# Mosfet_Driver_Circuit.net
KiCad netlist of a schematic drawn in Altium Designer
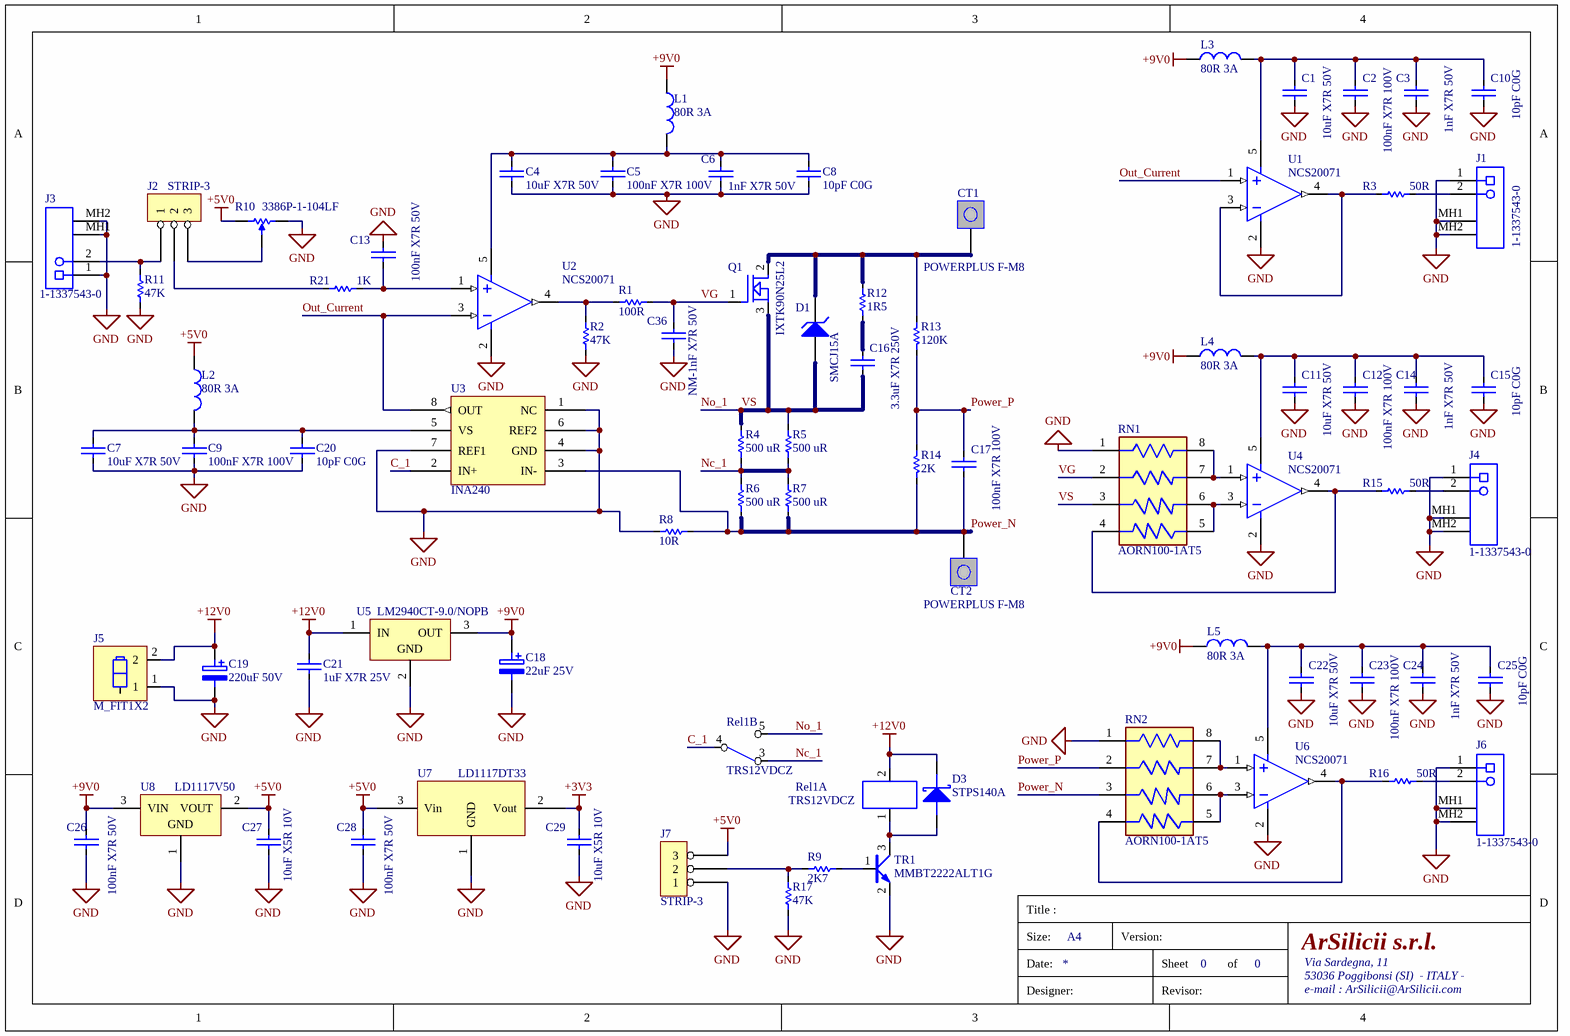
[diagram p0: Mosfet_Driver_Circuit.SchDoc]

(export (version "E")
  (design (tool "Eeschema 10.0.6"))
  (components
    (comp (ref "C1")
      (value "10uF X7R 50V")
      (footprint "1206")
      (description "Capacità")
      (fields
        (field (name "1 SUPPLIER PART NUMBER") "CL31B106KBHNNNE")
        (field (name "ARSILICII PART NUMBER") "CPC0232011")
      )
      (libsource (lib "Library_20-02-20") (part "CAP_10uF X7R 50V_1206"))
    )
    (comp (ref "C2")
      (value "100nF X7R 100V")
      (footprint "0805")
      (description "Capacità")
      (fields
        (field (name "1 SUPPLIER PART NUMBER") "CL21B104KCFSFNG")
        (field (name "2 SUPPLIER PART NUMBER") "1907331")
      )
      (libsource (lib "Library_20-02-20") (part "CAP_100nF X7R 100V_0805"))
    )
    (comp (ref "C3")
      (value "1nF X7R 50V")
      (footprint "0805")
      (description "Capacità")
      (fields
        (field (name "1 SUPPLIER PART NUMBER") "B37941K5102K60")
        (field (name "2 SUPPLIER PART NUMBER") "0805B102K5CT")
      )
      (libsource (lib "Library_20-02-20") (part "CAP_1nF X7R 50V_0805"))
    )
    (comp (ref "C4")
      (value "10uF X7R 50V")
      (footprint "1206")
      (description "Capacità")
      (fields
        (field (name "1 SUPPLIER PART NUMBER") "CL31B106KBHNNNE")
        (field (name "ARSILICII PART NUMBER") "CPC0232011")
      )
      (libsource (lib "Library_20-02-20") (part "CAP_10uF X7R 50V_1206"))
    )
    (comp (ref "C5")
      (value "100nF X7R 100V")
      (footprint "0805")
      (description "Capacità")
      (fields
        (field (name "1 SUPPLIER PART NUMBER") "CL21B104KCFSFNG")
        (field (name "2 SUPPLIER PART NUMBER") "1907331")
      )
      (libsource (lib "Library_20-02-20") (part "CAP_100nF X7R 100V_0805"))
    )
    (comp (ref "C6")
      (value "1nF X7R 50V")
      (footprint "0805")
      (description "Capacità")
      (fields
        (field (name "1 SUPPLIER PART NUMBER") "B37941K5102K60")
        (field (name "2 SUPPLIER PART NUMBER") "0805B102K5CT")
      )
      (libsource (lib "Library_20-02-20") (part "CAP_1nF X7R 50V_0805"))
    )
    (comp (ref "C7")
      (value "10uF X7R 50V")
      (footprint "1206")
      (description "Capacità")
      (fields
        (field (name "1 SUPPLIER PART NUMBER") "CL31B106KBHNNNE")
        (field (name "ARSILICII PART NUMBER") "CPC0232011")
      )
      (libsource (lib "Library_20-02-20") (part "CAP_10uF X7R 50V_1206"))
    )
    (comp (ref "C8")
      (value "10pF C0G")
      (footprint "0805")
      (description "Capacità")
      (fields (field (name "ARSILICII PART NUMBER") "CPC0614010"))
      (libsource (lib "Library_20-02-20") (part "CAP_10pF C0G_0805"))
    )
    (comp (ref "C9")
      (value "100nF X7R 100V")
      (footprint "0805")
      (description "Capacità")
      (fields
        (field (name "1 SUPPLIER PART NUMBER") "CL21B104KCFSFNG")
        (field (name "2 SUPPLIER PART NUMBER") "1907331")
      )
      (libsource (lib "Library_20-02-20") (part "CAP_100nF X7R 100V_0805"))
    )
    (comp (ref "C10")
      (value "10pF C0G")
      (footprint "0805")
      (description "Capacità")
      (fields (field (name "ARSILICII PART NUMBER") "CPC0614010"))
      (libsource (lib "Library_20-02-20") (part "CAP_10pF C0G_0805"))
    )
    (comp (ref "C11")
      (value "10uF X7R 50V")
      (footprint "1206")
      (description "Capacità")
      (fields
        (field (name "1 SUPPLIER PART NUMBER") "CL31B106KBHNNNE")
        (field (name "ARSILICII PART NUMBER") "CPC0232011")
      )
      (libsource (lib "Library_20-02-20") (part "CAP_10uF X7R 50V_1206"))
    )
    (comp (ref "C12")
      (value "100nF X7R 100V")
      (footprint "0805")
      (description "Capacità")
      (fields
        (field (name "1 SUPPLIER PART NUMBER") "CL21B104KCFSFNG")
        (field (name "2 SUPPLIER PART NUMBER") "1907331")
      )
      (libsource (lib "Library_20-02-20") (part "CAP_100nF X7R 100V_0805"))
    )
    (comp (ref "C13")
      (value "100nF X7R 50V")
      (footprint "0805")
      (description "Capacità")
      (fields
        (field (name "1 SUPPLIER PART NUMBER") "C0805C104K5RAC7800")
        (field (name "2 SUPPLIER PART NUMBER") "08055C104KAT2A AVX")
      )
      (libsource (lib "Library_20-02-20") (part "CAP_100nF X7R 50V_0805"))
    )
    (comp (ref "C14")
      (value "1nF X7R 50V")
      (footprint "0805")
      (description "Capacità")
      (fields
        (field (name "1 SUPPLIER PART NUMBER") "B37941K5102K60")
        (field (name "2 SUPPLIER PART NUMBER") "0805B102K5CT")
      )
      (libsource (lib "Library_20-02-20") (part "CAP_1nF X7R 50V_0805"))
    )
    (comp (ref "C15")
      (value "10pF C0G")
      (footprint "0805")
      (description "Capacità")
      (fields (field (name "ARSILICII PART NUMBER") "CPC0614010"))
      (libsource (lib "Library_20-02-20") (part "CAP_10pF C0G_0805"))
    )
    (comp (ref "C16")
      (value "3.3uF X7R 250V")
      (footprint "2220")
      (description "Capacità")
      (fields
        (field (name "1 SUPPLIER PART NUMBER") "2435506")
        (field (name "2 SUPPLIER PART NUMBER") "810-CGA9N3X7R2E105K")
      )
      (libsource (lib "Library_20-02-20") (part "CAP_1uF X7R 250V_2220"))
    )
    (comp (ref "C17")
      (value "100nF X7R 100V")
      (footprint "0805")
      (description "Capacità")
      (fields
        (field (name "1 SUPPLIER PART NUMBER") "CL21B104KCFSFNG")
        (field (name "2 SUPPLIER PART NUMBER") "1907331")
      )
      (libsource (lib "Library_20-02-20") (part "CAP_100nF X7R 100V_0805"))
    )
    (comp (ref "C18")
      (value "22uF 25V")
      (footprint "TANT_D")
      (description "Capacità polarizzata")
      (fields
        (field (name "1 SUPPLIER PART NUMBER") "KETT491D226K025AT")
        (field (name "ARSILICII PART NUMBER") "CPC0352022")
      )
      (libsource (lib "Library_20-02-20") (part "CAP_TANT_22uF 25V Case D"))
    )
    (comp (ref "C19")
      (value "220uF 50V")
      (footprint "C_G55")
      (description "Capacità polarizzata")
      (fields
        (field (name "2 SUPPLIER PART NUMBER") "5194346")
        (field (name "ARSILICII PART NUMBER") "CPC0402221")
      )
      (libsource (lib "Library_20-02-20") (part "CAP_EL_220uF 50V"))
    )
    (comp (ref "C20")
      (value "10pF C0G")
      (footprint "0805")
      (description "Capacità")
      (fields (field (name "ARSILICII PART NUMBER") "CPC0614010"))
      (libsource (lib "Library_20-02-20") (part "CAP_10pF C0G_0805"))
    )
    (comp (ref "C21")
      (value "1uF X7R 25V")
      (footprint "0805")
      (description "Capacità")
      (fields
        (field (name "1 SUPPLIER PART NUMBER") "CL21B105KAFNNNG")
        (field (name "ARSILICII PART NUMBER") "CPC0212002")
      )
      (libsource (lib "Library_20-02-20") (part "CAP_1uF X7R 25V_0805"))
    )
    (comp (ref "C22")
      (value "10uF X7R 50V")
      (footprint "1206")
      (description "Capacità")
      (fields
        (field (name "1 SUPPLIER PART NUMBER") "CL31B106KBHNNNE")
        (field (name "ARSILICII PART NUMBER") "CPC0232011")
      )
      (libsource (lib "Library_20-02-20") (part "CAP_10uF X7R 50V_1206"))
    )
    (comp (ref "C23")
      (value "100nF X7R 100V")
      (footprint "0805")
      (description "Capacità")
      (fields
        (field (name "1 SUPPLIER PART NUMBER") "CL21B104KCFSFNG")
        (field (name "2 SUPPLIER PART NUMBER") "1907331")
      )
      (libsource (lib "Library_20-02-20") (part "CAP_100nF X7R 100V_0805"))
    )
    (comp (ref "C24")
      (value "1nF X7R 50V")
      (footprint "0805")
      (description "Capacità")
      (fields
        (field (name "1 SUPPLIER PART NUMBER") "B37941K5102K60")
        (field (name "2 SUPPLIER PART NUMBER") "0805B102K5CT")
      )
      (libsource (lib "Library_20-02-20") (part "CAP_1nF X7R 50V_0805"))
    )
    (comp (ref "C25")
      (value "10pF C0G")
      (footprint "0805")
      (description "Capacità")
      (fields (field (name "ARSILICII PART NUMBER") "CPC0614010"))
      (libsource (lib "Library_20-02-20") (part "CAP_10pF C0G_0805"))
    )
    (comp (ref "C26")
      (value "100nF X7R 50V")
      (footprint "0805")
      (description "Capacità")
      (fields
        (field (name "1 SUPPLIER PART NUMBER") "C0805C104K5RAC7800")
        (field (name "2 SUPPLIER PART NUMBER") "08055C104KAT2A AVX")
      )
      (libsource (lib "Library_20-02-20") (part "CAP_100nF X7R 50V_0805"))
    )
    (comp (ref "C27")
      (value "10uF X5R 10V")
      (footprint "0805")
      (description "Capacità")
      (fields
        (field (name "1 SUPPLIER PART NUMBER") "CL21A106KPFNNNE")
        (field (name "ARSILICII PART NUMBER") "CPC0212010")
      )
      (libsource (lib "Library_20-02-20") (part "CAP_10uF X5R 10V_0805"))
    )
    (comp (ref "C28")
      (value "100nF X7R 50V")
      (footprint "0805")
      (description "Capacità")
      (fields
        (field (name "1 SUPPLIER PART NUMBER") "C0805C104K5RAC7800")
        (field (name "2 SUPPLIER PART NUMBER") "08055C104KAT2A AVX")
      )
      (libsource (lib "Library_20-02-20") (part "CAP_100nF X7R 50V_0805"))
    )
    (comp (ref "C29")
      (value "10uF X5R 10V")
      (footprint "0805")
      (description "Capacità")
      (fields
        (field (name "1 SUPPLIER PART NUMBER") "CL21A106KPFNNNE")
        (field (name "ARSILICII PART NUMBER") "CPC0212010")
      )
      (libsource (lib "Library_20-02-20") (part "CAP_10uF X5R 10V_0805"))
    )
    (comp (ref "C36")
      (value "NM-1nF X7R 50V")
      (footprint "0805")
      (description "Capacità")
      (fields
        (field (name "1 SUPPLIER PART NUMBER") "B37941K5102K60")
        (field (name "2 SUPPLIER PART NUMBER") "0805B102K5CT")
      )
      (libsource (lib "Library_20-02-20") (part "CAP_1nF X7R 50V_0805"))
    )
    (comp (ref "CT1")
      (value "POWERPLUS F-M8")
      (footprint "PowerPlus M8")
      (description "Singolo contatto")
      (fields
        (field (name "1 SUPPLIER PART NUMBER") "S98978")
        (field (name "ARSILICII PART NUMBER") "QC04000180")
      )
      (libsource (lib "Library_20-02-20") (part "PAD_POWERPLUS F-M8"))
    )
    (comp (ref "CT2")
      (value "POWERPLUS F-M8")
      (footprint "PowerPlus M8")
      (description "Singolo contatto")
      (fields
        (field (name "1 SUPPLIER PART NUMBER") "S98978")
        (field (name "ARSILICII PART NUMBER") "QC04000180")
      )
      (libsource (lib "") (part "PAD_POWERPLUS F-M8_1"))
    )
    (comp (ref "D1")
      (value "SMCJ15A")
      (footprint "LFUS-DO-214AB-2_V")
      (fields (field (name "MANUFACTURER") "Littelfuse"))
      (libsource (lib "Altium Content Vault") (part "DZEN-AK-2"))
    )
    (comp (ref "D3")
      (value "STPS140A")
      (footprint "SMA")
      (description "Diodo Schottky")
      (fields
        (field (name "MANUFACTURER") "STMicroelectronics")
        (field (name "1 SUPPLIER PART NUMBER") "STMSTPS140A")
      )
      (libsource (lib "Library_20-02-20") (part "DIODE SCHOTTKY_STPS140A"))
    )
    (comp (ref "J1")
      (value "1-1337543-0")
      (footprint "TECO-1-1337543-0_V")
      (fields (field (name "MANUFACTURER") "TE Connectivity"))
      (libsource (lib "Altium Content Vault") (part "CN-1P-F-R2_A"))
    )
    (comp (ref "J2")
      (value "STRIP-3")
      (footprint "SIP-3")
      (libsource (lib "Library_20-02-20") (part "HEADER 3"))
    )
    (comp (ref "J3")
      (value "1-1337543-0")
      (footprint "TECO-1-1337543-0_V")
      (fields (field (name "MANUFACTURER") "TE Connectivity"))
      (libsource (lib "") (part "CN-1P-F-R2_A_1"))
    )
    (comp (ref "J4")
      (value "1-1337543-0")
      (footprint "TECO-1-1337543-0_V")
      (fields (field (name "MANUFACTURER") "TE Connectivity"))
      (libsource (lib "Altium Content Vault") (part "CN-1P-F-R2_A"))
    )
    (comp (ref "J5")
      (value "M_FIT1X2")
      (footprint "M_FIT_JR1X2V")
      (description "Mini Fit Junior 2 poli")
      (fields (field (name "ARSILICII PART NUMBER") "QA02006000") (field (name "MANUFACTURER") "Molex"))
      (libsource (lib "Library_20-02-20") (part "M_FIT1X2"))
    )
    (comp (ref "J6")
      (value "1-1337543-0")
      (footprint "TECO-1-1337543-0_V")
      (fields (field (name "MANUFACTURER") "TE Connectivity"))
      (libsource (lib "Altium Content Vault") (part "CN-1P-F-R2_A"))
    )
    (comp (ref "J7") (value "STRIP-3") (footprint "SIP-3") (libsource (lib "") (part "HEADER 3_1")))
    (comp (ref "L1")
      (value "80R 3A")
      (footprint "1206")
      (description "Ferrite")
      (fields
        (field (name "1 SUPPLIER PART NUMBER") "3275550P")
        (field (name "ARSILICII PART NUMBER") "CPF0006000")
      )
      (libsource (lib "Library_20-02-20") (part "Ferrite 80R 3A"))
    )
    (comp (ref "L2")
      (value "80R 3A")
      (footprint "1206")
      (description "Ferrite")
      (fields
        (field (name "1 SUPPLIER PART NUMBER") "3275550P")
        (field (name "ARSILICII PART NUMBER") "CPF0006000")
      )
      (libsource (lib "Library_20-02-20") (part "Ferrite 80R 3A"))
    )
    (comp (ref "L3")
      (value "80R 3A")
      (footprint "1206")
      (description "Ferrite")
      (fields
        (field (name "1 SUPPLIER PART NUMBER") "3275550P")
        (field (name "ARSILICII PART NUMBER") "CPF0006000")
      )
      (libsource (lib "Library_20-02-20") (part "Ferrite 80R 3A"))
    )
    (comp (ref "L4")
      (value "80R 3A")
      (footprint "1206")
      (description "Ferrite")
      (fields
        (field (name "1 SUPPLIER PART NUMBER") "3275550P")
        (field (name "ARSILICII PART NUMBER") "CPF0006000")
      )
      (libsource (lib "Library_20-02-20") (part "Ferrite 80R 3A"))
    )
    (comp (ref "L5")
      (value "80R 3A")
      (footprint "1206")
      (description "Ferrite")
      (fields
        (field (name "1 SUPPLIER PART NUMBER") "3275550P")
        (field (name "ARSILICII PART NUMBER") "CPF0006000")
      )
      (libsource (lib "Library_20-02-20") (part "Ferrite 80R 3A"))
    )
    (comp (ref "Q1")
      (value "IXTK90N25L2")
      (footprint "Library_20-02-20:TO-247")
      (description "MOS CANALE N-250V-90A Linear")
      (fields
        (field (name "1 SUPPLIER PART NUMBER") "PB90N06S4-04")
        (field (name "2 SUPPLIER PART NUMBER") "826-9042P")
      )
      (libsource (lib "Library_20-02-20") (part "IXTK90N25L2"))
    )
    (comp (ref "R1")
      (value "100R")
      (footprint "0805")
      (description "Resistenza")
      (libsource (lib "Library_20-02-20") (part "RES_SMD"))
    )
    (comp (ref "R2")
      (value "47K")
      (footprint "0805")
      (description "Resistenza")
      (libsource (lib "Library_20-02-20") (part "RES_SMD"))
    )
    (comp (ref "R3")
      (value "50R")
      (footprint "0805")
      (description "Resistenza")
      (libsource (lib "Library_20-02-20") (part "RES_SMD"))
    )
    (comp (ref "R4")
      (value "500 uR")
      (footprint "2512")
      (description "Resistenza")
      (libsource (lib "Library_20-02-20") (part "RES_SMD"))
    )
    (comp (ref "R5")
      (value "500 uR")
      (footprint "2512")
      (description "Resistenza")
      (libsource (lib "Library_20-02-20") (part "RES_SMD"))
    )
    (comp (ref "R6")
      (value "500 uR")
      (footprint "2512")
      (description "Resistenza")
      (libsource (lib "Library_20-02-20") (part "RES_SMD"))
    )
    (comp (ref "R7")
      (value "500 uR")
      (footprint "2512")
      (description "Resistenza")
      (libsource (lib "Library_20-02-20") (part "RES_SMD"))
    )
    (comp (ref "R8")
      (value "10R")
      (footprint "1206")
      (description "Resistenza")
      (libsource (lib "Library_20-02-20") (part "RES_SMD"))
    )
    (comp (ref "R9")
      (value "2K7")
      (footprint "0805")
      (description "Resistenza")
      (libsource (lib "Library_20-02-20") (part "RES_SMD"))
    )
    (comp (ref "R10")
      (value "3386P-1-104LF")
      (footprint "BOUR-3386P")
      (fields (field (name "TOLERANCE") "10%") (field (name "MANUFACTURER") "Bourns"))
      (libsource (lib "Altium Content Vault") (part "RES-ADJ-3_A"))
    )
    (comp (ref "R11")
      (value "47K")
      (footprint "0805")
      (description "Resistenza")
      (libsource (lib "Library_20-02-20") (part "RES_SMD"))
    )
    (comp (ref "R12")
      (value "1R5")
      (footprint "2512")
      (description "Resistenza")
      (libsource (lib "Library_20-02-20") (part "RES_SMD"))
    )
    (comp (ref "R13")
      (value "120K")
      (footprint "2512")
      (description "Resistenza")
      (libsource (lib "Library_20-02-20") (part "RES_SMD"))
    )
    (comp (ref "R14")
      (value "2K")
      (footprint "2512")
      (description "Resistenza")
      (libsource (lib "Library_20-02-20") (part "RES_SMD"))
    )
    (comp (ref "R15")
      (value "50R")
      (footprint "0805")
      (description "Resistenza")
      (libsource (lib "Library_20-02-20") (part "RES_SMD"))
    )
    (comp (ref "R16")
      (value "50R")
      (footprint "0805")
      (description "Resistenza")
      (libsource (lib "Library_20-02-20") (part "RES_SMD"))
    )
    (comp (ref "R17")
      (value "47K")
      (footprint "0805")
      (description "Resistenza")
      (libsource (lib "Library_20-02-20") (part "RES_SMD"))
    )
    (comp (ref "R21")
      (value "1K")
      (footprint "0805")
      (description "Resistenza")
      (libsource (lib "Library_20-02-20") (part "RES_SMD"))
    )
    (comp (ref "Rel1")
      (value "TRS12VDCZ")
      (footprint "RELE_TRS")
      (description "Relay")
      (fields
        (field (name "2 SUPPLIER PART NUMBER") "FRS3M C-S DC12V")
        (field (name "3 SUPPLIER PART NUMBER") "R504D/012Z1F")
      )
      (libsource (lib "Library_20-02-20") (part "RELE'_TRS12VDCZ"))
    )
    (comp (ref "RN1")
      (value "AORN100-1AT5")
      (footprint "FP-AORN100-1AT5-IPC_C")
      (description "RES NETWORK 4 RES MULT OHM 8SOIC")
      (fields (field (name "MANUFACTURER") "Vishay") (field (name "TOLERANCE") "0.1%"))
      (libsource (lib "Altium Content Vault") (part "8441eaa576eb2593bca60d5301712c1"))
    )
    (comp (ref "RN2")
      (value "AORN100-1AT5")
      (footprint "FP-AORN100-1AT5-IPC_C")
      (description "RES NETWORK 4 RES MULT OHM 8SOIC")
      (fields (field (name "MANUFACTURER") "Vishay") (field (name "TOLERANCE") "0.1%"))
      (libsource (lib "Altium Content Vault") (part "8441eaa576eb2593bca60d5301712c1"))
    )
    (comp (ref "TR1")
      (value "MMBT2222ALT1G")
      (footprint "SOT-23")
      (description "NPN Transistor")
      (fields
        (field (name "1 SUPPLIER PART NUMBER") "SCGMMBT2222ALT1G")
        (field (name "2 SUPPLIER PART NUMBER") "1459098")
      )
      (libsource (lib "Library_20-02-20") (part "NPN_MMBT2222ALT1G"))
    )
    (comp (ref "U1")
      (value "NCS20071")
      (footprint "SOT-553-5")
      (description "Rail-to-Rail Input/Output, 3 MHz Op Amps")
      (fields
        (field (name "1 SUPPLIER PART NUMBER") "MCP6021-E/SN-ND")
        (field (name "MANUFACTURER") "Microchip Technology")
      )
      (libsource (lib "Library_20-02-20") (part "NCS20071"))
    )
    (comp (ref "U2")
      (value "NCS20071")
      (footprint "SOT-553-5")
      (description "Rail-to-Rail Input/Output, 3 MHz Op Amps")
      (fields
        (field (name "1 SUPPLIER PART NUMBER") "MCP6021-E/SN-ND")
        (field (name "MANUFACTURER") "Microchip Technology")
      )
      (libsource (lib "Library_20-02-20") (part "NCS20071"))
    )
    (comp (ref "U3")
      (value "INA240")
      (footprint "TSSOP-8")
      (description "Current sense amplifier")
      (libsource (lib "Library_20-02-20") (part "INA240"))
    )
    (comp (ref "U4")
      (value "NCS20071")
      (footprint "SOT-553-5")
      (description "Rail-to-Rail Input/Output, 3 MHz Op Amps")
      (fields
        (field (name "1 SUPPLIER PART NUMBER") "MCP6021-E/SN-ND")
        (field (name "MANUFACTURER") "Microchip Technology")
      )
      (libsource (lib "Library_20-02-20") (part "NCS20071"))
    )
    (comp (ref "U5")
      (value "LM2940CT-9.0/NOPB")
      (footprint "NDE0003A")
      (description "1A Low Dropout Regulator, 3-pin TO-220, Pb-Free")
      (fields (field (name "MANUFACTURER") "Texas Instruments"))
      (libsource (lib "Altium Content Vault") (part "PM-REG-LM2940-SIL3"))
    )
    (comp (ref "U6")
      (value "NCS20071")
      (footprint "SOT-553-5")
      (description "Rail-to-Rail Input/Output, 3 MHz Op Amps")
      (fields
        (field (name "1 SUPPLIER PART NUMBER") "MCP6021-E/SN-ND")
        (field (name "MANUFACTURER") "Microchip Technology")
      )
      (libsource (lib "Library_20-02-20") (part "NCS20071"))
    )
    (comp (ref "U7")
      (value "LD1117DT33")
      (footprint "TO-252-7805")
      (description "Regolatore Low Dropout")
      (fields
        (field (name "1 SUPPLIER PART NUMBER") "LD1117DT33TR TO252-3")
        (field (name "ARSILICII PART NUMBER") "IC01000010")
      )
      (libsource (lib "Library_20-02-20") (part "LD1117DT33"))
    )
    (comp (ref "U8")
      (value "LD1117V50")
      (footprint "TO220")
      (description "Fixed Low Drop Positive Voltage Regulator, 5V, 3-Pin TO-220")
      (libsource (lib "Altium Content Vault") (part "PM-REG-LD1117V-SIL3"))
    )
  )
  (nets
    (net (code "1") (name "+3V3") (class "Default")
      (node (ref "C29") (pin "1") (pintype "passive"))
      (node (ref "U7") (pin "2") (pinfunction "Vout_2") (pintype "power_in"))
    )
    (net (code "2") (name "+5V0") (class "Default")
      (node (ref "C27") (pin "1") (pintype "passive"))
      (node (ref "C28") (pin "1") (pintype "passive"))
      (node (ref "J7") (pin "3") (pinfunction "3_3") (pintype "passive"))
      (node (ref "L2") (pin "1") (pinfunction "1_1") (pintype "passive"))
      (node (ref "R10") (pin "1") (pinfunction "1_1") (pintype "passive"))
      (node (ref "U7") (pin "3") (pinfunction "Vin_3") (pintype "power_in"))
      (node (ref "U8") (pin "2") (pinfunction "VOUT_2") (pintype "power_in"))
    )
    (net (code "3") (name "+9V0") (class "Default")
      (node (ref "C18") (pin "1") (pintype "passive"))
      (node (ref "C26") (pin "1") (pintype "passive"))
      (node (ref "L1") (pin "1") (pinfunction "1_1") (pintype "passive"))
      (node (ref "L3") (pin "1") (pinfunction "1_1") (pintype "passive"))
      (node (ref "L4") (pin "1") (pinfunction "1_1") (pintype "passive"))
      (node (ref "L5") (pin "1") (pinfunction "1_1") (pintype "passive"))
      (node (ref "U5") (pin "3") (pinfunction "OUT_3") (pintype "power_in"))
      (node (ref "U8") (pin "3") (pinfunction "VIN_3") (pintype "power_in"))
    )
    (net (code "4") (name "+12V0") (class "Default")
      (node (ref "C19") (pin "1") (pintype "passive"))
      (node (ref "C21") (pin "1") (pintype "passive"))
      (node (ref "D3") (pin "K") (pinfunction "K_K") (pintype "passive"))
      (node (ref "J5") (pin "2") (pinfunction "2_2") (pintype "passive"))
      (node (ref "Rel1") (pin "2") (pintype "passive"))
      (node (ref "U5") (pin "1") (pinfunction "IN_1") (pintype "power_in"))
    )
    (net (code "5") (name "/C_1") (class "Default")
      (node (ref "Rel1") (pin "4") (pintype "passive"))
      (node (ref "U3") (pin "2") (pinfunction "IN+_2") (pintype "tri_state"))
    )
    (net (code "6") (name "/Nc_1") (class "Default")
      (node (ref "R4") (pin "2") (pinfunction "2_2") (pintype "passive"))
      (node (ref "R5") (pin "2") (pinfunction "2_2") (pintype "passive"))
      (node (ref "R6") (pin "1") (pinfunction "1_1") (pintype "passive"))
      (node (ref "R7") (pin "1") (pinfunction "1_1") (pintype "passive"))
      (node (ref "Rel1") (pin "3") (pintype "passive"))
    )
    (net (code "7") (name "/No_1") (class "Default")
      (node (ref "C16") (pin "2") (pintype "passive"))
      (node (ref "D1") (pin "1") (pinfunction "A_1") (pintype "passive"))
      (node (ref "Q1") (pin "3") (pinfunction "SOURCE_3") (pintype "passive"))
      (node (ref "R4") (pin "1") (pinfunction "1_1") (pintype "passive"))
      (node (ref "R5") (pin "1") (pinfunction "1_1") (pintype "passive"))
      (node (ref "RN1") (pin "3") (pinfunction "3_3") (pintype "passive"))
      (node (ref "Rel1") (pin "5") (pintype "passive"))
    )
    (net (code "8") (name "/Out_Current") (class "Default")
      (node (ref "U1") (pin "1") (pintype "input"))
      (node (ref "U2") (pin "3") (pintype "input"))
      (node (ref "U3") (pin "8") (pinfunction "OUT_8") (pintype "output"))
    )
    (net (code "9") (name "/Power_N") (class "Default")
      (node (ref "C17") (pin "2") (pintype "passive"))
      (node (ref "CT2") (pin "1") (pinfunction "1_1") (pintype "passive"))
      (node (ref "R14") (pin "2") (pinfunction "2_2") (pintype "passive"))
      (node (ref "R6") (pin "2") (pinfunction "2_2") (pintype "passive"))
      (node (ref "R7") (pin "2") (pinfunction "2_2") (pintype "passive"))
      (node (ref "R8") (pin "1") (pinfunction "1_1") (pintype "passive"))
      (node (ref "RN2") (pin "3") (pinfunction "3_3") (pintype "passive"))
      (node (ref "U3") (pin "3") (pinfunction "IN-_3") (pintype "tri_state"))
    )
    (net (code "10") (name "/Power_P") (class "Default")
      (node (ref "C17") (pin "1") (pintype "passive"))
      (node (ref "R13") (pin "2") (pinfunction "2_2") (pintype "passive"))
      (node (ref "R14") (pin "1") (pinfunction "1_1") (pintype "passive"))
      (node (ref "RN2") (pin "2") (pinfunction "2_2") (pintype "passive"))
    )
    (net (code "11") (name "/VG") (class "Default")
      (node (ref "C36") (pin "1") (pintype "passive"))
      (node (ref "Q1") (pin "1") (pinfunction "GATE_1") (pintype "passive"))
      (node (ref "R1") (pin "2") (pinfunction "2_2") (pintype "passive"))
      (node (ref "RN1") (pin "2") (pinfunction "2_2") (pintype "passive"))
    )
    (net (code "12") (name "GND") (class "Default")
      (node (ref "C1") (pin "2") (pintype "passive"))
      (node (ref "C10") (pin "2") (pintype "passive"))
      (node (ref "C11") (pin "2") (pintype "passive"))
      (node (ref "C12") (pin "2") (pintype "passive"))
      (node (ref "C13") (pin "1") (pintype "passive"))
      (node (ref "C14") (pin "2") (pintype "passive"))
      (node (ref "C15") (pin "2") (pintype "passive"))
      (node (ref "C18") (pin "2") (pintype "passive"))
      (node (ref "C19") (pin "2") (pintype "passive"))
      (node (ref "C2") (pin "2") (pintype "passive"))
      (node (ref "C20") (pin "2") (pintype "passive"))
      (node (ref "C21") (pin "2") (pintype "passive"))
      (node (ref "C22") (pin "2") (pintype "passive"))
      (node (ref "C23") (pin "2") (pintype "passive"))
      (node (ref "C24") (pin "2") (pintype "passive"))
      (node (ref "C25") (pin "2") (pintype "passive"))
      (node (ref "C26") (pin "2") (pintype "passive"))
      (node (ref "C27") (pin "2") (pintype "passive"))
      (node (ref "C28") (pin "2") (pintype "passive"))
      (node (ref "C29") (pin "2") (pintype "passive"))
      (node (ref "C3") (pin "2") (pintype "passive"))
      (node (ref "C36") (pin "2") (pintype "passive"))
      (node (ref "C4") (pin "2") (pintype "passive"))
      (node (ref "C5") (pin "2") (pintype "passive"))
      (node (ref "C6") (pin "2") (pintype "passive"))
      (node (ref "C7") (pin "2") (pintype "passive"))
      (node (ref "C8") (pin "2") (pintype "passive"))
      (node (ref "C9") (pin "2") (pintype "passive"))
      (node (ref "J1") (pin "1") (pinfunction "1_1") (pintype "passive"))
      (node (ref "J1") (pin "MH1") (pinfunction "MH1_MH1") (pintype "passive"))
      (node (ref "J1") (pin "MH2") (pinfunction "MH2_MH2") (pintype "passive"))
      (node (ref "J3") (pin "1") (pinfunction "1_1") (pintype "passive"))
      (node (ref "J3") (pin "MH1") (pinfunction "MH1_MH1") (pintype "passive"))
      (node (ref "J3") (pin "MH2") (pinfunction "MH2_MH2") (pintype "passive"))
      (node (ref "J4") (pin "1") (pinfunction "1_1") (pintype "passive"))
      (node (ref "J4") (pin "MH1") (pinfunction "MH1_MH1") (pintype "passive"))
      (node (ref "J4") (pin "MH2") (pinfunction "MH2_MH2") (pintype "passive"))
      (node (ref "J5") (pin "1") (pinfunction "1_1") (pintype "passive"))
      (node (ref "J6") (pin "1") (pinfunction "1_1") (pintype "passive"))
      (node (ref "J6") (pin "MH1") (pinfunction "MH1_MH1") (pintype "passive"))
      (node (ref "J6") (pin "MH2") (pinfunction "MH2_MH2") (pintype "passive"))
      (node (ref "J7") (pin "1") (pinfunction "1_1") (pintype "passive"))
      (node (ref "R10") (pin "3") (pinfunction "3_3") (pintype "passive"))
      (node (ref "R11") (pin "1") (pinfunction "1_1") (pintype "passive"))
      (node (ref "R17") (pin "2") (pinfunction "2_2") (pintype "passive"))
      (node (ref "R2") (pin "2") (pinfunction "2_2") (pintype "passive"))
      (node (ref "R8") (pin "2") (pinfunction "2_2") (pintype "passive"))
      (node (ref "RN1") (pin "1") (pinfunction "1_1") (pintype "passive"))
      (node (ref "RN2") (pin "1") (pinfunction "1_1") (pintype "passive"))
      (node (ref "TR1") (pin "2") (pinfunction "E_2") (pintype "passive"))
      (node (ref "U1") (pin "2") (pintype "power_in"))
      (node (ref "U2") (pin "2") (pintype "power_in"))
      (node (ref "U3") (pin "1") (pinfunction "NC_1") (pintype "passive"))
      (node (ref "U3") (pin "4") (pinfunction "GND_4") (pintype "power_in"))
      (node (ref "U3") (pin "6") (pinfunction "REF2_6") (pintype "passive"))
      (node (ref "U3") (pin "7") (pinfunction "REF1_7") (pintype "passive"))
      (node (ref "U4") (pin "2") (pintype "power_in"))
      (node (ref "U5") (pin "2") (pinfunction "GND_2") (pintype "power_in"))
      (node (ref "U6") (pin "2") (pintype "power_in"))
      (node (ref "U7") (pin "1") (pinfunction "GND_1") (pintype "power_in"))
      (node (ref "U8") (pin "1") (pinfunction "GND_1") (pintype "power_in"))
    )
    (net (code "13") (name "Net-(C1-Pad1)") (class "Default")
      (node (ref "C1") (pin "1") (pintype "passive"))
      (node (ref "C10") (pin "1") (pintype "passive"))
      (node (ref "C2") (pin "1") (pintype "passive"))
      (node (ref "C3") (pin "1") (pintype "passive"))
      (node (ref "L3") (pin "2") (pinfunction "2_2") (pintype "passive"))
      (node (ref "U1") (pin "5") (pintype "power_in"))
    )
    (net (code "14") (name "Net-(C4-Pad1)") (class "Default")
      (node (ref "C4") (pin "1") (pintype "passive"))
      (node (ref "C5") (pin "1") (pintype "passive"))
      (node (ref "C6") (pin "1") (pintype "passive"))
      (node (ref "C8") (pin "1") (pintype "passive"))
      (node (ref "L1") (pin "2") (pinfunction "2_2") (pintype "passive"))
      (node (ref "U2") (pin "5") (pintype "power_in"))
    )
    (net (code "15") (name "Net-(C11-Pad1)") (class "Default")
      (node (ref "C11") (pin "1") (pintype "passive"))
      (node (ref "C12") (pin "1") (pintype "passive"))
      (node (ref "C14") (pin "1") (pintype "passive"))
      (node (ref "C15") (pin "1") (pintype "passive"))
      (node (ref "L4") (pin "2") (pinfunction "2_2") (pintype "passive"))
      (node (ref "U4") (pin "5") (pintype "power_in"))
    )
    (net (code "16") (name "Net-(C13-Pad2)") (class "Default")
      (node (ref "C13") (pin "2") (pintype "passive"))
      (node (ref "R21") (pin "2") (pinfunction "2_2") (pintype "passive"))
      (node (ref "U2") (pin "1") (pintype "input"))
    )
    (net (code "17") (name "Net-(C16-Pad1)") (class "Default")
      (node (ref "C16") (pin "1") (pintype "passive"))
      (node (ref "R12") (pin "2") (pinfunction "2_2") (pintype "passive"))
    )
    (net (code "18") (name "Net-(C22-Pad1)") (class "Default")
      (node (ref "C22") (pin "1") (pintype "passive"))
      (node (ref "C23") (pin "1") (pintype "passive"))
      (node (ref "C24") (pin "1") (pintype "passive"))
      (node (ref "C25") (pin "1") (pintype "passive"))
      (node (ref "L5") (pin "2") (pinfunction "2_2") (pintype "passive"))
      (node (ref "U6") (pin "5") (pintype "power_in"))
    )
    (net (code "19") (name "Net-(D1-K)") (class "Default")
      (node (ref "CT1") (pin "1") (pinfunction "1_1") (pintype "passive"))
      (node (ref "D1") (pin "2") (pinfunction "K_2") (pintype "passive"))
      (node (ref "Q1") (pin "2") (pinfunction "DRAIN_2") (pintype "passive"))
      (node (ref "R12") (pin "1") (pinfunction "1_1") (pintype "passive"))
      (node (ref "R13") (pin "1") (pinfunction "1_1") (pintype "passive"))
    )
    (net (code "20") (name "Net-(J1-Pad2)") (class "Default")
      (node (ref "J1") (pin "2") (pinfunction "2_2") (pintype "passive"))
      (node (ref "R3") (pin "1") (pinfunction "1_1") (pintype "passive"))
    )
    (net (code "21") (name "Net-(J2-Pad1)") (class "Default")
      (node (ref "J2") (pin "1") (pinfunction "1_1") (pintype "passive"))
      (node (ref "J3") (pin "2") (pinfunction "2_2") (pintype "passive"))
      (node (ref "R11") (pin "2") (pinfunction "2_2") (pintype "passive"))
    )
    (net (code "22") (name "Net-(J2-Pad2)") (class "Default")
      (node (ref "J2") (pin "2") (pinfunction "2_2") (pintype "passive"))
      (node (ref "R21") (pin "1") (pinfunction "1_1") (pintype "passive"))
    )
    (net (code "23") (name "Net-(J2-Pad3)") (class "Default")
      (node (ref "J2") (pin "3") (pinfunction "3_3") (pintype "passive"))
      (node (ref "R10") (pin "2") (pinfunction "2_2") (pintype "passive"))
    )
    (net (code "24") (name "Net-(J4-Pad2)") (class "Default")
      (node (ref "J4") (pin "2") (pinfunction "2_2") (pintype "passive"))
      (node (ref "R15") (pin "1") (pinfunction "1_1") (pintype "passive"))
    )
    (net (code "25") (name "Net-(J6-Pad2)") (class "Default")
      (node (ref "J6") (pin "2") (pinfunction "2_2") (pintype "passive"))
      (node (ref "R16") (pin "1") (pinfunction "1_1") (pintype "passive"))
    )
    (net (code "26") (name "Net-(J7-Pad2)") (class "Default")
      (node (ref "J7") (pin "2") (pinfunction "2_2") (pintype "passive"))
      (node (ref "R17") (pin "1") (pinfunction "1_1") (pintype "passive"))
      (node (ref "R9") (pin "2") (pinfunction "2_2") (pintype "passive"))
    )
    (net (code "27") (name "Net-(R1-Pad1)") (class "Default")
      (node (ref "R1") (pin "1") (pinfunction "1_1") (pintype "passive"))
      (node (ref "R2") (pin "1") (pinfunction "1_1") (pintype "passive"))
      (node (ref "U2") (pin "4") (pintype "output"))
    )
    (net (code "28") (name "Net-(R3-Pad2)") (class "Default")
      (node (ref "R3") (pin "2") (pinfunction "2_2") (pintype "passive"))
      (node (ref "U1") (pin "3") (pintype "input"))
      (node (ref "U1") (pin "4") (pintype "output"))
    )
    (net (code "29") (name "Net-(R15-Pad2)") (class "Default")
      (node (ref "R15") (pin "2") (pinfunction "2_2") (pintype "passive"))
      (node (ref "RN1") (pin "4") (pinfunction "4_4") (pintype "passive"))
      (node (ref "U4") (pin "4") (pintype "output"))
    )
    (net (code "30") (name "Net-(R16-Pad2)") (class "Default")
      (node (ref "R16") (pin "2") (pinfunction "2_2") (pintype "passive"))
      (node (ref "RN2") (pin "4") (pinfunction "4_4") (pintype "passive"))
      (node (ref "U6") (pin "4") (pintype "output"))
    )
    (net (code "31") (name "Net-(RN1-Pad5)") (class "Default")
      (node (ref "RN1") (pin "5") (pinfunction "5_5") (pintype "passive"))
      (node (ref "RN1") (pin "6") (pinfunction "6_6") (pintype "passive"))
      (node (ref "U4") (pin "3") (pintype "input"))
    )
    (net (code "32") (name "Net-(RN1-Pad7)") (class "Default")
      (node (ref "RN1") (pin "7") (pinfunction "7_7") (pintype "passive"))
      (node (ref "RN1") (pin "8") (pinfunction "8_8") (pintype "passive"))
      (node (ref "U4") (pin "1") (pintype "input"))
    )
    (net (code "33") (name "Net-(RN2-Pad5)") (class "Default")
      (node (ref "RN2") (pin "5") (pinfunction "5_5") (pintype "passive"))
      (node (ref "RN2") (pin "6") (pinfunction "6_6") (pintype "passive"))
      (node (ref "U6") (pin "3") (pintype "input"))
    )
    (net (code "34") (name "Net-(RN2-Pad7)") (class "Default")
      (node (ref "RN2") (pin "7") (pinfunction "7_7") (pintype "passive"))
      (node (ref "RN2") (pin "8") (pinfunction "8_8") (pintype "passive"))
      (node (ref "U6") (pin "1") (pintype "input"))
    )
    (net (code "35") (name "Net-(TR1-B)") (class "Default")
      (node (ref "R9") (pin "1") (pinfunction "1_1") (pintype "passive"))
      (node (ref "TR1") (pin "1") (pinfunction "B_1") (pintype "passive"))
    )
    (net (code "36") (name "Net-(TR1-C)") (class "Default")
      (node (ref "D3") (pin "A") (pinfunction "A_A") (pintype "passive"))
      (node (ref "Rel1") (pin "1") (pintype "passive"))
      (node (ref "TR1") (pin "3") (pinfunction "C_3") (pintype "passive"))
    )
    (net (code "37") (name "Net-(U3-VS)") (class "Default")
      (node (ref "C20") (pin "1") (pintype "passive"))
      (node (ref "C7") (pin "1") (pintype "passive"))
      (node (ref "C9") (pin "1") (pintype "passive"))
      (node (ref "L2") (pin "2") (pinfunction "2_2") (pintype "passive"))
      (node (ref "U3") (pin "5") (pinfunction "VS_5") (pintype "power_in"))
    )
  )
)
